# Adapter.net
KiCad netlist of a schematic drawn in Altium Designer
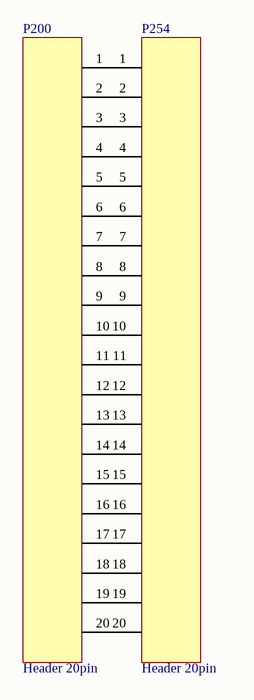
[diagram p0: Adapter.SchDoc]

(export (version "E")
  (design (tool "Eeschema 10.0.6"))
  (components
    (comp (ref "P200")
      (value "Header 20pin")
      (footprint "Header 2.00 2x10")
      (libsource (lib "") (part "Header 20pin_1"))
    )
    (comp (ref "P254")
      (value "Header 20pin")
      (footprint "Header 2.54 2x10 rect pads")
      (libsource (lib "Adapter") (part "Header 20pin"))
    )
  )
  (nets
    (net (code "1") (name "Net-(P200-Pad1)") (class "Default")
      (node (ref "P200") (pin "1") (pinfunction "1_1") (pintype "passive"))
      (node (ref "P254") (pin "1") (pinfunction "1_1") (pintype "passive"))
    )
    (net (code "2") (name "Net-(P200-Pad2)") (class "Default")
      (node (ref "P200") (pin "2") (pinfunction "2_2") (pintype "passive"))
      (node (ref "P254") (pin "2") (pinfunction "2_2") (pintype "passive"))
    )
    (net (code "3") (name "Net-(P200-Pad3)") (class "Default")
      (node (ref "P200") (pin "3") (pinfunction "3_3") (pintype "passive"))
      (node (ref "P254") (pin "3") (pinfunction "3_3") (pintype "passive"))
    )
    (net (code "4") (name "Net-(P200-Pad4)") (class "Default")
      (node (ref "P200") (pin "4") (pinfunction "4_4") (pintype "passive"))
      (node (ref "P254") (pin "4") (pinfunction "4_4") (pintype "passive"))
    )
    (net (code "5") (name "Net-(P200-Pad5)") (class "Default")
      (node (ref "P200") (pin "5") (pinfunction "5_5") (pintype "passive"))
      (node (ref "P254") (pin "5") (pinfunction "5_5") (pintype "passive"))
    )
    (net (code "6") (name "Net-(P200-Pad6)") (class "Default")
      (node (ref "P200") (pin "6") (pinfunction "6_6") (pintype "passive"))
      (node (ref "P254") (pin "6") (pinfunction "6_6") (pintype "passive"))
    )
    (net (code "7") (name "Net-(P200-Pad7)") (class "Default")
      (node (ref "P200") (pin "7") (pinfunction "7_7") (pintype "passive"))
      (node (ref "P254") (pin "7") (pinfunction "7_7") (pintype "passive"))
    )
    (net (code "8") (name "Net-(P200-Pad8)") (class "Default")
      (node (ref "P200") (pin "8") (pinfunction "8_8") (pintype "passive"))
      (node (ref "P254") (pin "8") (pinfunction "8_8") (pintype "passive"))
    )
    (net (code "9") (name "Net-(P200-Pad9)") (class "Default")
      (node (ref "P200") (pin "9") (pinfunction "9_9") (pintype "passive"))
      (node (ref "P254") (pin "9") (pinfunction "9_9") (pintype "passive"))
    )
    (net (code "10") (name "Net-(P200-Pad10)") (class "Default")
      (node (ref "P200") (pin "10") (pinfunction "10_10") (pintype "passive"))
      (node (ref "P254") (pin "10") (pinfunction "10_10") (pintype "passive"))
    )
    (net (code "11") (name "Net-(P200-Pad11)") (class "Default")
      (node (ref "P200") (pin "11") (pinfunction "11_11") (pintype "passive"))
      (node (ref "P254") (pin "11") (pinfunction "11_11") (pintype "passive"))
    )
    (net (code "12") (name "Net-(P200-Pad12)") (class "Default")
      (node (ref "P200") (pin "12") (pinfunction "12_12") (pintype "passive"))
      (node (ref "P254") (pin "12") (pinfunction "12_12") (pintype "passive"))
    )
    (net (code "13") (name "Net-(P200-Pad13)") (class "Default")
      (node (ref "P200") (pin "13") (pinfunction "13_13") (pintype "passive"))
      (node (ref "P254") (pin "13") (pinfunction "13_13") (pintype "passive"))
    )
    (net (code "14") (name "Net-(P200-Pad14)") (class "Default")
      (node (ref "P200") (pin "14") (pinfunction "14_14") (pintype "passive"))
      (node (ref "P254") (pin "14") (pinfunction "14_14") (pintype "passive"))
    )
    (net (code "15") (name "Net-(P200-Pad15)") (class "Default")
      (node (ref "P200") (pin "15") (pinfunction "15_15") (pintype "passive"))
      (node (ref "P254") (pin "15") (pinfunction "15_15") (pintype "passive"))
    )
    (net (code "16") (name "Net-(P200-Pad16)") (class "Default")
      (node (ref "P200") (pin "16") (pinfunction "16_16") (pintype "passive"))
      (node (ref "P254") (pin "16") (pinfunction "16_16") (pintype "passive"))
    )
    (net (code "17") (name "Net-(P200-Pad17)") (class "Default")
      (node (ref "P200") (pin "17") (pinfunction "17_17") (pintype "passive"))
      (node (ref "P254") (pin "17") (pinfunction "17_17") (pintype "passive"))
    )
    (net (code "18") (name "Net-(P200-Pad18)") (class "Default")
      (node (ref "P200") (pin "18") (pinfunction "18_18") (pintype "passive"))
      (node (ref "P254") (pin "18") (pinfunction "18_18") (pintype "passive"))
    )
    (net (code "19") (name "Net-(P200-Pad19)") (class "Default")
      (node (ref "P200") (pin "19") (pinfunction "19_19") (pintype "passive"))
      (node (ref "P254") (pin "19") (pinfunction "19_19") (pintype "passive"))
    )
    (net (code "20") (name "Net-(P200-Pad20)") (class "Default")
      (node (ref "P200") (pin "20") (pinfunction "20_20") (pintype "passive"))
      (node (ref "P254") (pin "20") (pinfunction "20_20") (pintype "passive"))
    )
  )
)
